# PSPS_AVNC_SRD_central-2020-10-12.net
KiCad netlist of a schematic drawn in EAGLE
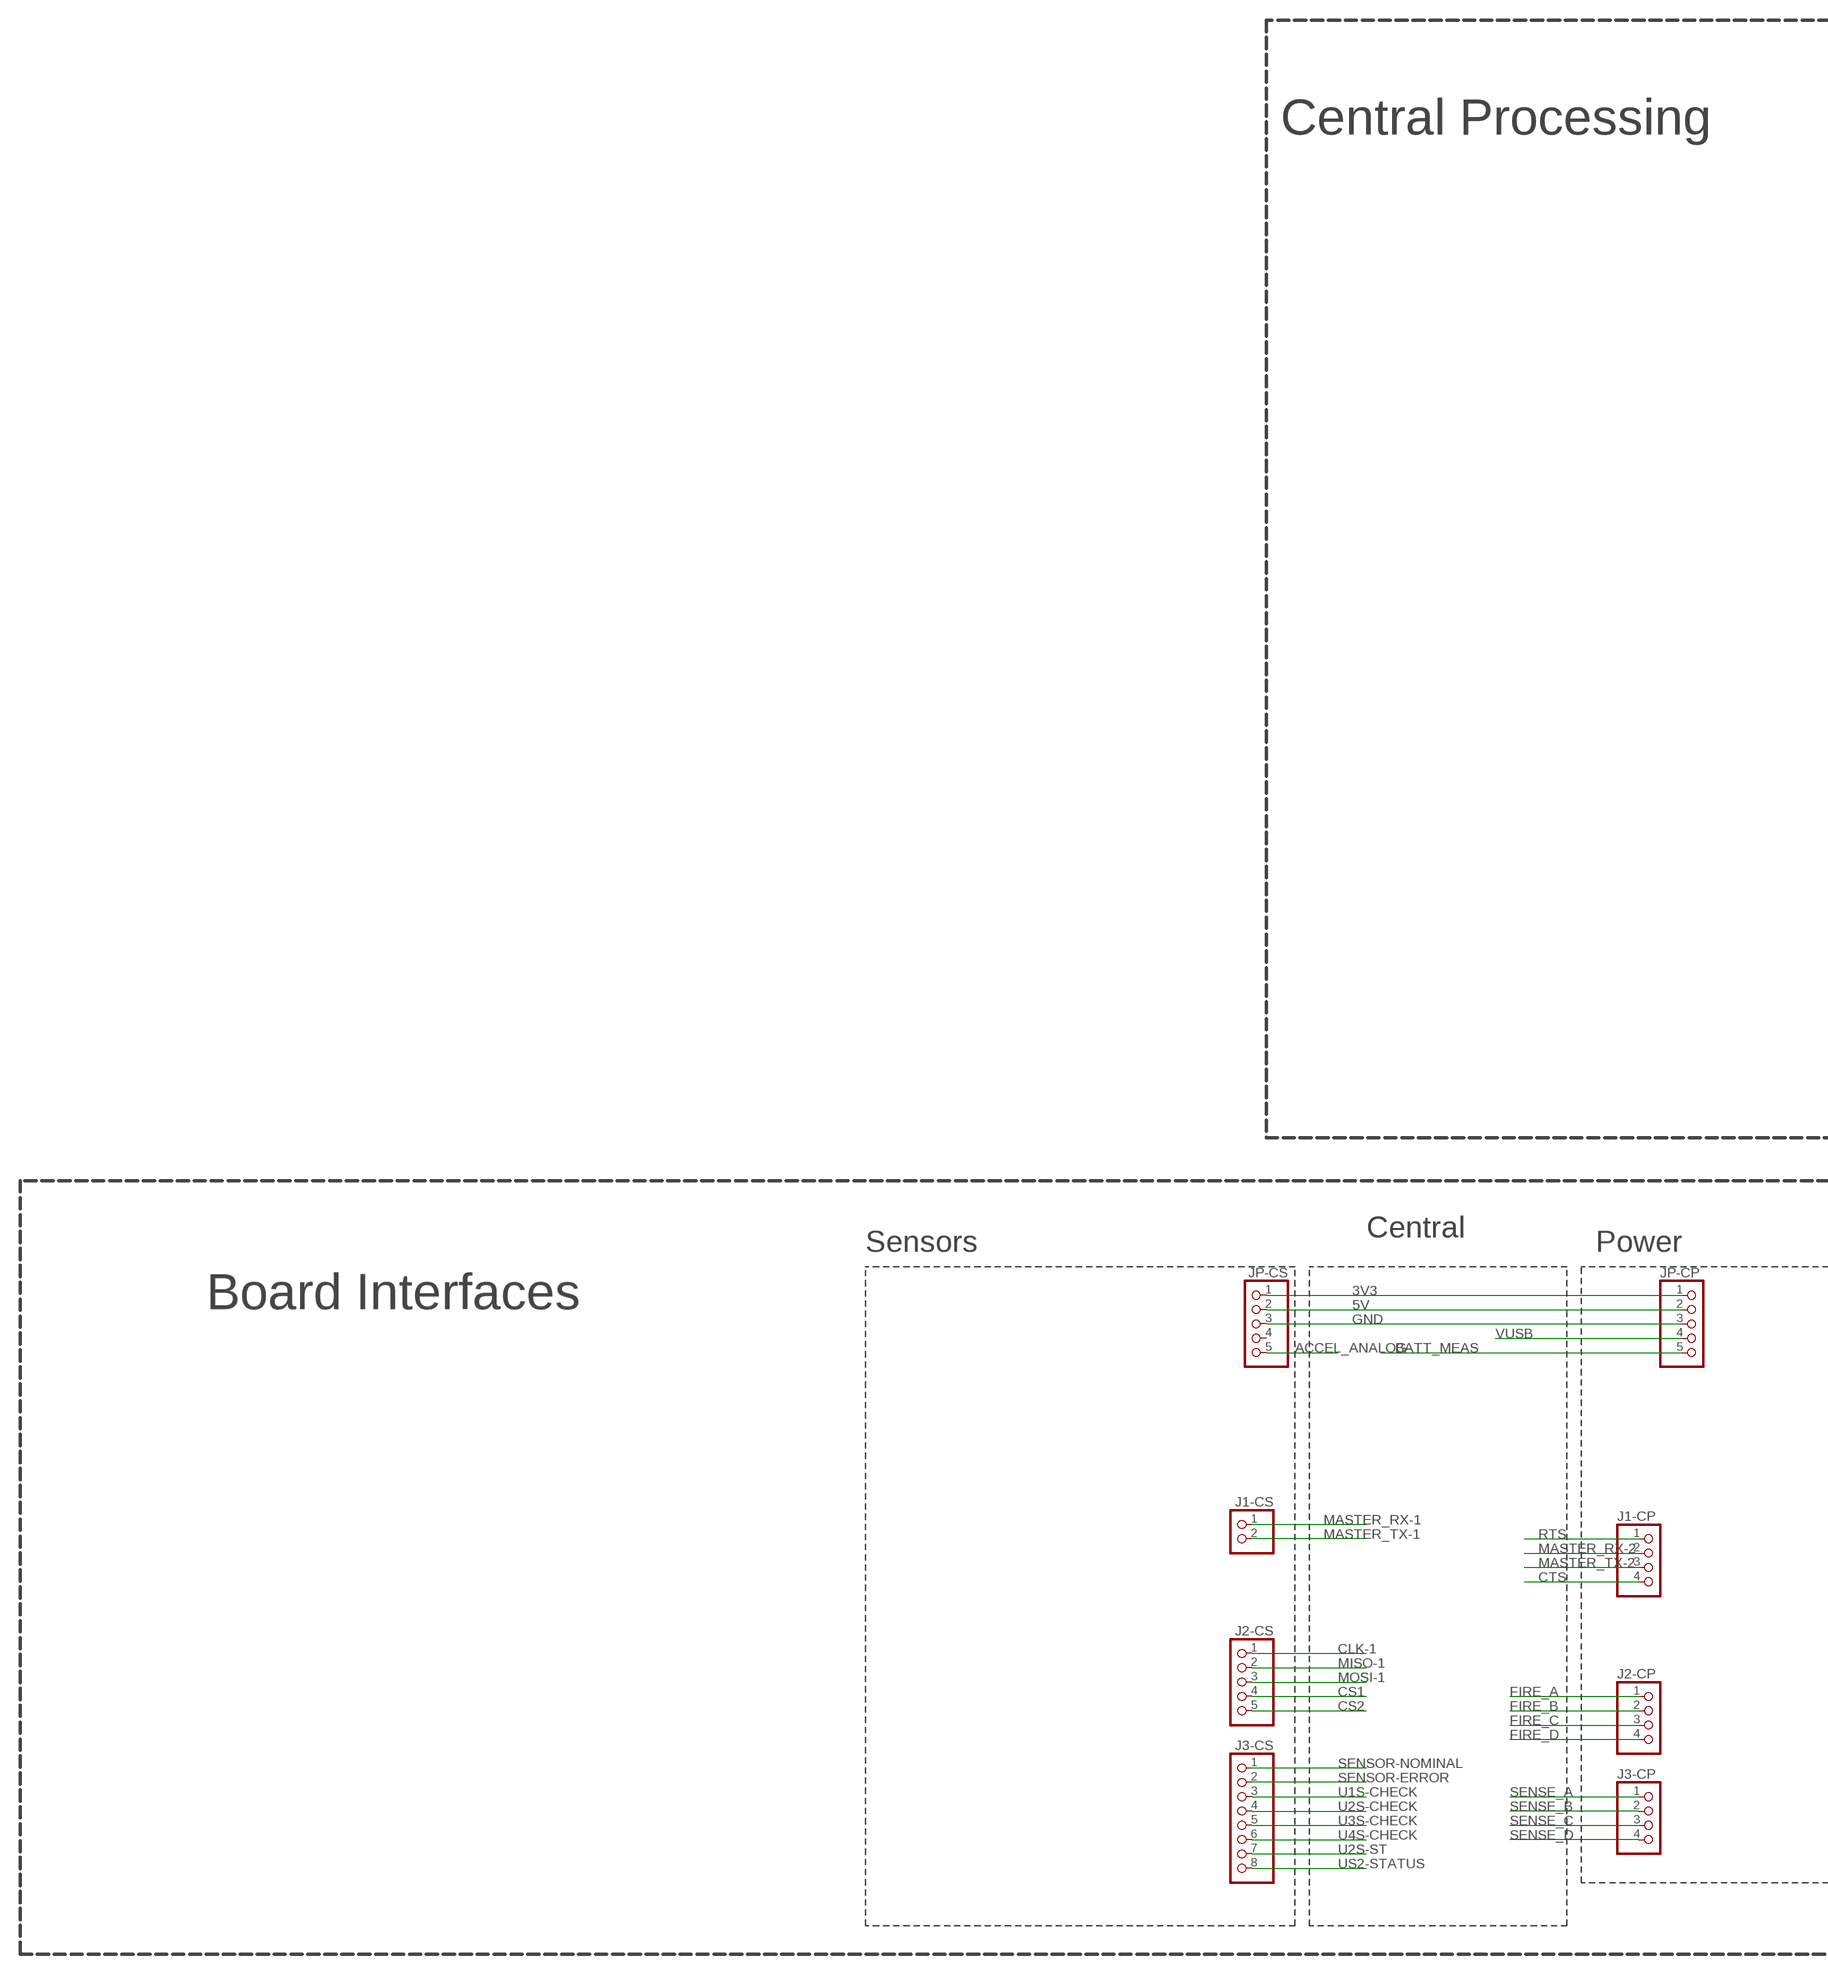
[diagram p0: schematic, sheet 1, part 1 of 2]
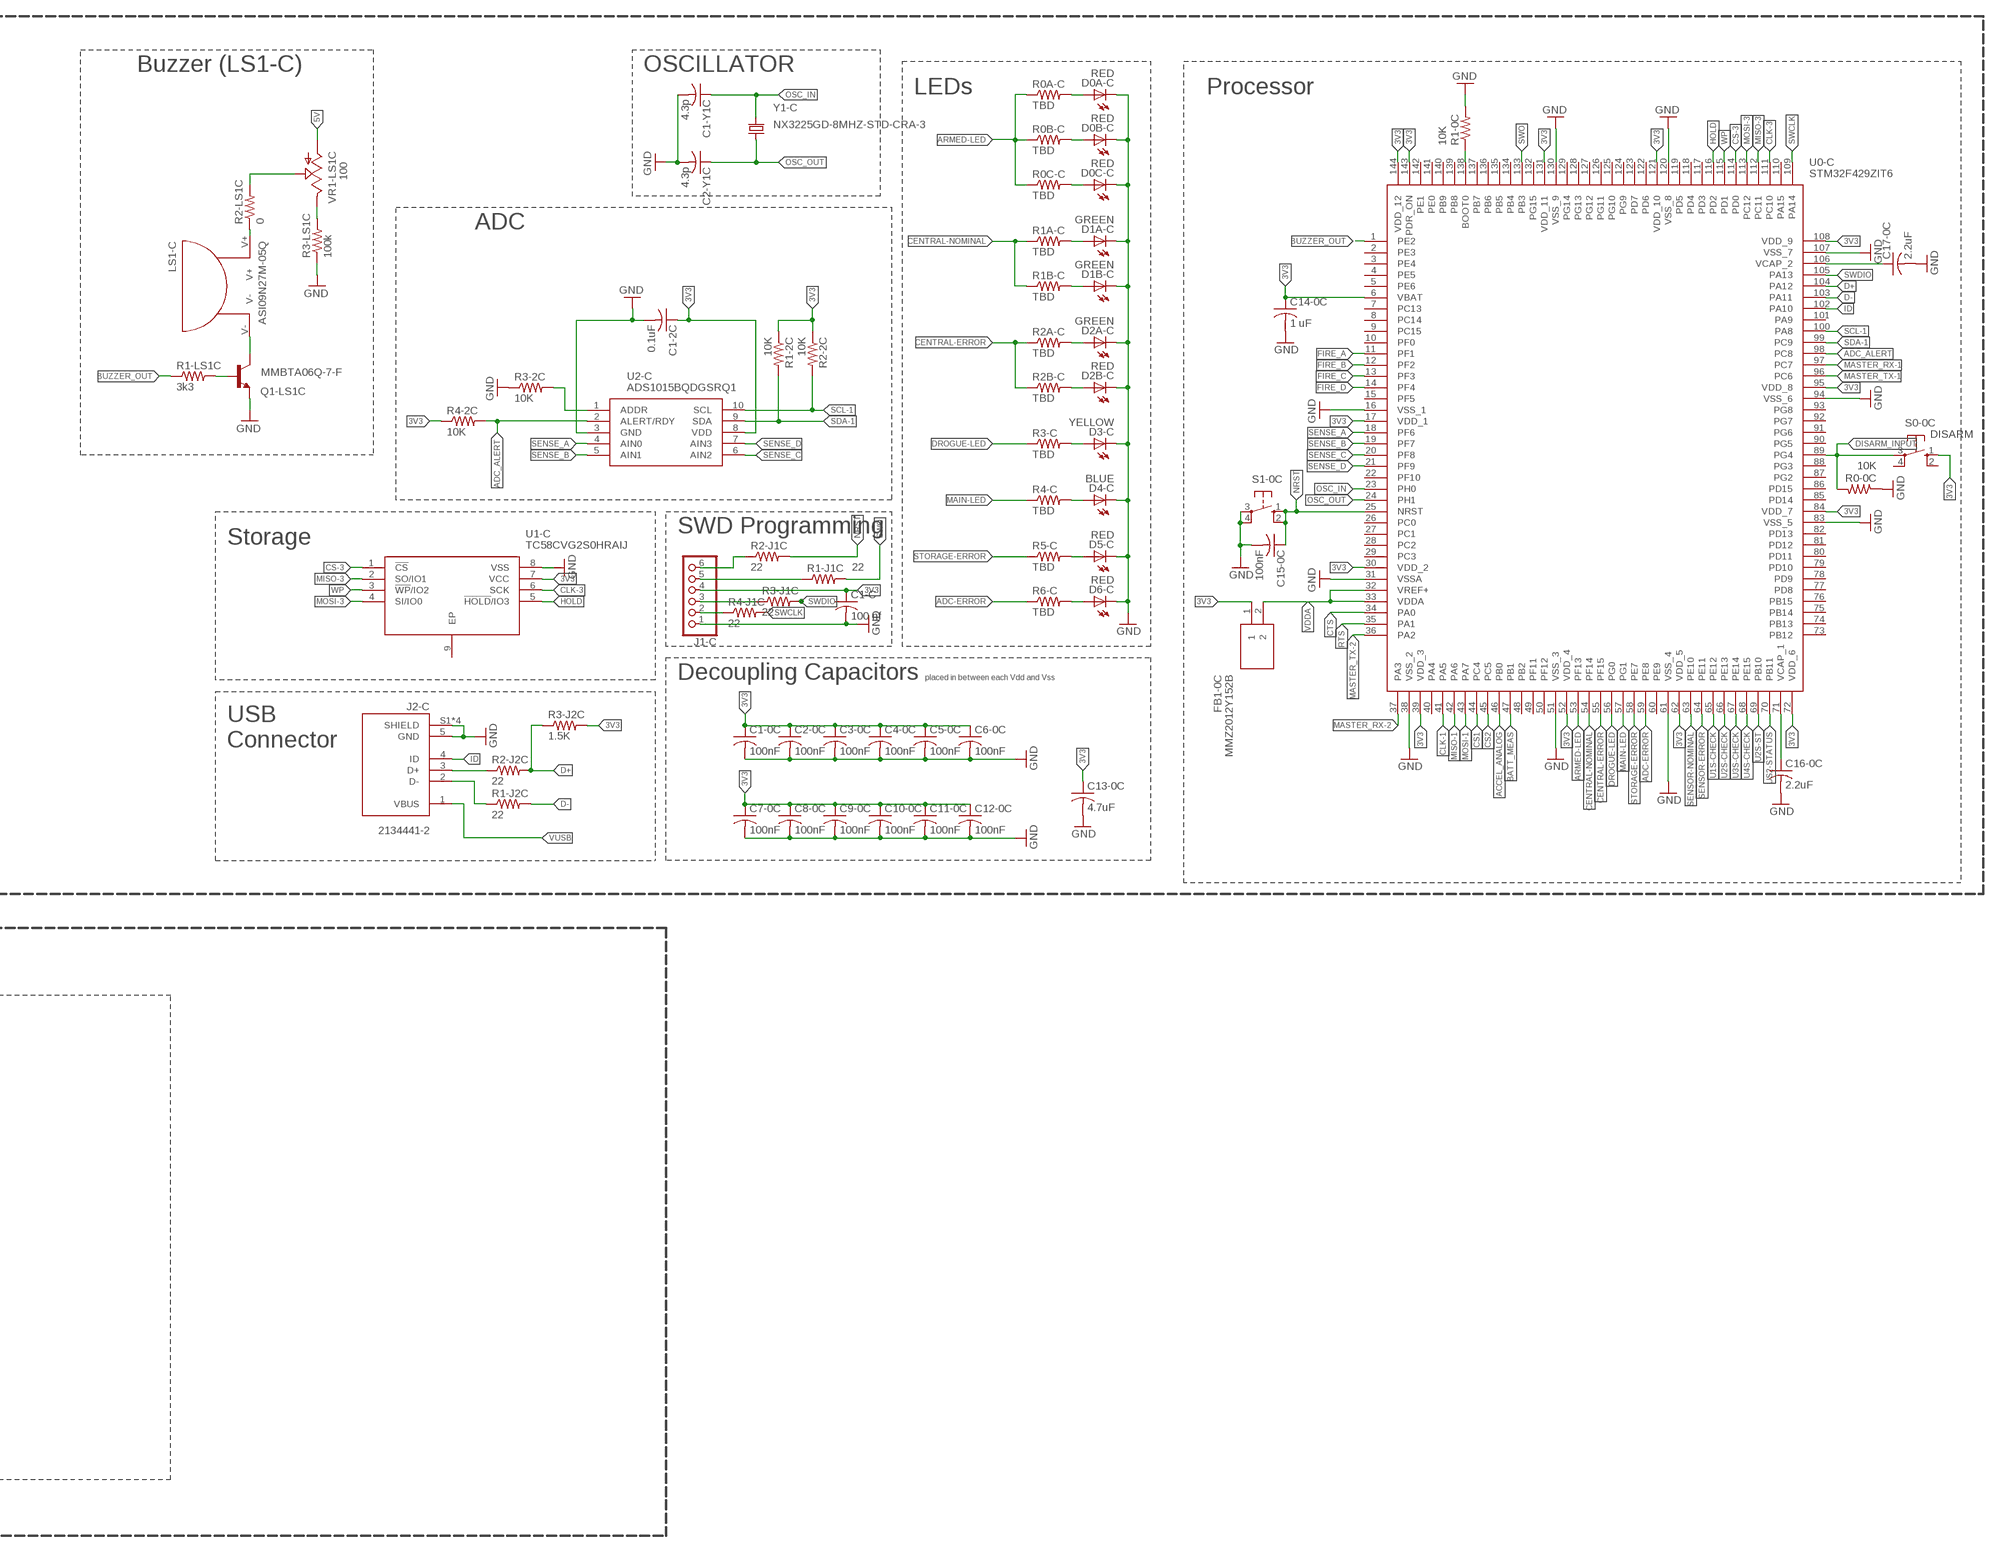
[diagram p1: schematic, sheet 1, part 2 of 2]

(export (version "E")
  (design (tool "Eeschema 10.0.6"))
  (components
    (comp (ref "C1-0C")
      (value "100nF")
      (footprint "eagle-import:C0805")
      (libsource (lib "eagle-import") (part "C-USC0805"))
    )
    (comp (ref "C1-2C")
      (value "0.1uF")
      (footprint "eagle-import:C0805")
      (libsource (lib "eagle-import") (part "C-USC0805"))
    )
    (comp (ref "C1-C")
      (value "100 nf")
      (footprint "eagle-import:C0805")
      (libsource (lib "eagle-import") (part "C-USC0805"))
    )
    (comp (ref "C1-Y1C")
      (value "4.3p")
      (footprint "eagle-import:C0805")
      (libsource (lib "eagle-import") (part "C-USC0805"))
    )
    (comp (ref "C2-0C")
      (value "100nF")
      (footprint "eagle-import:C0805")
      (libsource (lib "eagle-import") (part "C-USC0805"))
    )
    (comp (ref "C2-Y1C")
      (value "4.3p")
      (footprint "eagle-import:C0805")
      (libsource (lib "eagle-import") (part "C-USC0805"))
    )
    (comp (ref "C3-0C")
      (value "100nF")
      (footprint "eagle-import:C0805")
      (libsource (lib "eagle-import") (part "C-USC0805"))
    )
    (comp (ref "C4-0C")
      (value "100nF")
      (footprint "eagle-import:C0805")
      (libsource (lib "eagle-import") (part "C-USC0805"))
    )
    (comp (ref "C5-0C")
      (value "100nF")
      (footprint "eagle-import:C0805")
      (libsource (lib "eagle-import") (part "C-USC0805"))
    )
    (comp (ref "C6-0C")
      (value "100nF")
      (footprint "eagle-import:C0805")
      (libsource (lib "eagle-import") (part "C-USC0805"))
    )
    (comp (ref "C7-0C")
      (value "100nF")
      (footprint "eagle-import:C0805")
      (libsource (lib "eagle-import") (part "C-USC0805"))
    )
    (comp (ref "C8-0C")
      (value "100nF")
      (footprint "eagle-import:C0805")
      (libsource (lib "eagle-import") (part "C-USC0805"))
    )
    (comp (ref "C9-0C")
      (value "100nF")
      (footprint "eagle-import:C0805")
      (libsource (lib "eagle-import") (part "C-USC0805"))
    )
    (comp (ref "C10-0C")
      (value "100nF")
      (footprint "eagle-import:C0805")
      (libsource (lib "eagle-import") (part "C-USC0805"))
    )
    (comp (ref "C11-0C")
      (value "100nF")
      (footprint "eagle-import:C0805")
      (libsource (lib "eagle-import") (part "C-USC0805"))
    )
    (comp (ref "C12-0C")
      (value "100nF")
      (footprint "eagle-import:C0805")
      (libsource (lib "eagle-import") (part "C-USC0805"))
    )
    (comp (ref "C13-0C")
      (value "4.7uF")
      (footprint "eagle-import:C0805")
      (libsource (lib "eagle-import") (part "C-USC0805"))
    )
    (comp (ref "C14-0C")
      (value "1 uF")
      (footprint "eagle-import:C0805")
      (libsource (lib "eagle-import") (part "C-USC0805"))
    )
    (comp (ref "C15-0C")
      (value "100nF")
      (footprint "eagle-import:C0805")
      (libsource (lib "eagle-import") (part "C-USC0805"))
    )
    (comp (ref "C16-0C")
      (value "2.2uF")
      (footprint "eagle-import:C0805")
      (libsource (lib "eagle-import") (part "C-USC0805"))
    )
    (comp (ref "C17-0C")
      (value "2.2uF")
      (footprint "eagle-import:C0805")
      (libsource (lib "eagle-import") (part "C-USC0805"))
    )
    (comp (ref "D0A-C")
      (value "RED")
      (footprint "eagle-import:CHIPLED_0805")
      (libsource (lib "eagle-import") (part "LEDCHIPLED_0805"))
    )
    (comp (ref "D0B-C")
      (value "RED")
      (footprint "eagle-import:CHIPLED_0805")
      (libsource (lib "eagle-import") (part "LEDCHIPLED_0805"))
    )
    (comp (ref "D0C-C")
      (value "RED")
      (footprint "eagle-import:CHIPLED_0805")
      (libsource (lib "eagle-import") (part "LEDCHIPLED_0805"))
    )
    (comp (ref "D1A-C")
      (value "GREEN")
      (footprint "eagle-import:CHIPLED_0805")
      (libsource (lib "eagle-import") (part "LEDCHIPLED_0805"))
    )
    (comp (ref "D1B-C")
      (value "GREEN")
      (footprint "eagle-import:CHIPLED_0805")
      (libsource (lib "eagle-import") (part "LEDCHIPLED_0805"))
    )
    (comp (ref "D2A-C")
      (value "GREEN")
      (footprint "eagle-import:CHIPLED_0805")
      (libsource (lib "eagle-import") (part "LEDCHIPLED_0805"))
    )
    (comp (ref "D2B-C")
      (value "RED")
      (footprint "eagle-import:CHIPLED_0805")
      (libsource (lib "eagle-import") (part "LEDCHIPLED_0805"))
    )
    (comp (ref "D3-C")
      (value "YELLOW")
      (footprint "eagle-import:CHIPLED_0805")
      (libsource (lib "eagle-import") (part "LEDCHIPLED_0805"))
    )
    (comp (ref "D4-C")
      (value "BLUE")
      (footprint "eagle-import:CHIPLED_0805")
      (libsource (lib "eagle-import") (part "LEDCHIPLED_0805"))
    )
    (comp (ref "D5-C")
      (value "RED")
      (footprint "eagle-import:CHIPLED_0805")
      (libsource (lib "eagle-import") (part "LEDCHIPLED_0805"))
    )
    (comp (ref "D6-C")
      (value "RED")
      (footprint "eagle-import:CHIPLED_0805")
      (libsource (lib "eagle-import") (part "LEDCHIPLED_0805"))
    )
    (comp (ref "FB1-0C")
      (value "MMZ2012Y152B")
      (footprint "eagle-import:BEADC2012X105N")
      (fields (field (name "MOUSER_PART_NUMBER") "810-MMZ2012Y152B"))
      (libsource (lib "eagle-import") (part "MMZ2012Y152B"))
    )
    (comp (ref "J1-C")
      (value "PINHD-1X6")
      (footprint "eagle-import:1X06")
      (libsource (lib "eagle-import") (part "PINHD-1X6"))
    )
    (comp (ref "J1-CP")
      (value "PINHD-1X4")
      (footprint "eagle-import:1X04")
      (libsource (lib "eagle-import") (part "PINHD-1X4"))
    )
    (comp (ref "J1-CS")
      (value "PINHD-1X2")
      (footprint "eagle-import:1X02")
      (libsource (lib "eagle-import") (part "PINHD-1X2"))
    )
    (comp (ref "J2-C")
      (value "2134441-2")
      (footprint "eagle-import:TE_2134441-2")
      (fields (field (name "DIGI-KEY_PART_NUMBER") "A118104CT-ND") (field (name "MF") "TE Connectivity"))
      (libsource (lib "eagle-import") (part "2134441-2"))
    )
    (comp (ref "J2-CP")
      (value "PINHD-1X4")
      (footprint "eagle-import:1X04")
      (libsource (lib "eagle-import") (part "PINHD-1X4"))
    )
    (comp (ref "J2-CS")
      (value "PINHD-1X5")
      (footprint "eagle-import:1X05")
      (libsource (lib "eagle-import") (part "PINHD-1X5"))
    )
    (comp (ref "J3-CP")
      (value "PINHD-1X4")
      (footprint "eagle-import:1X04")
      (libsource (lib "eagle-import") (part "PINHD-1X4"))
    )
    (comp (ref "J3-CS")
      (value "PINHD-1X8")
      (footprint "eagle-import:1X08")
      (libsource (lib "eagle-import") (part "PINHD-1X8"))
    )
    (comp (ref "JP-CP")
      (value "PINHD-1X5")
      (footprint "eagle-import:1X05")
      (libsource (lib "eagle-import") (part "PINHD-1X5"))
    )
    (comp (ref "JP-CS")
      (value "PINHD-1X5")
      (footprint "eagle-import:1X05")
      (libsource (lib "eagle-import") (part "PINHD-1X5"))
    )
    (comp (ref "LS1-C")
      (value "ASI09N27M-05Q")
      (footprint "eagle-import:ASI09N27M-05Q")
      (libsource (lib "eagle-import") (part "ASI09N27M-05Q"))
    )
    (comp (ref "Q1-LS1C")
      (value "MMBTA06Q-7-F")
      (footprint "eagle-import:SOT23")
      (libsource (lib "eagle-import") (part "NPN_TRANSISTOR"))
    )
    (comp (ref "R0-0C")
      (value "10K")
      (footprint "eagle-import:R0805")
      (libsource (lib "eagle-import") (part "R-US_R0805"))
    )
    (comp (ref "R0A-C")
      (value "TBD")
      (footprint "eagle-import:M0805")
      (libsource (lib "eagle-import") (part "R-US_M0805"))
    )
    (comp (ref "R0B-C")
      (value "TBD")
      (footprint "eagle-import:M0805")
      (libsource (lib "eagle-import") (part "R-US_M0805"))
    )
    (comp (ref "R0C-C")
      (value "TBD")
      (footprint "eagle-import:M0805")
      (libsource (lib "eagle-import") (part "R-US_M0805"))
    )
    (comp (ref "R1-0C")
      (value "10K")
      (footprint "eagle-import:R0805")
      (libsource (lib "eagle-import") (part "R-US_R0805"))
    )
    (comp (ref "R1-2C")
      (value "10K")
      (footprint "eagle-import:R0805")
      (libsource (lib "eagle-import") (part "R-US_R0805"))
    )
    (comp (ref "R1-J1C")
      (value "22")
      (footprint "eagle-import:M0805")
      (libsource (lib "eagle-import") (part "R-US_M0805"))
    )
    (comp (ref "R1-J2C")
      (value "22")
      (footprint "eagle-import:M0805")
      (libsource (lib "eagle-import") (part "R-US_M0805"))
    )
    (comp (ref "R1-LS1C")
      (value "3k3")
      (footprint "eagle-import:R0805")
      (libsource (lib "eagle-import") (part "resistor_348_R-US_R0805"))
    )
    (comp (ref "R1A-C")
      (value "TBD")
      (footprint "eagle-import:M0805")
      (libsource (lib "eagle-import") (part "R-US_M0805"))
    )
    (comp (ref "R1B-C")
      (value "TBD")
      (footprint "eagle-import:M0805")
      (libsource (lib "eagle-import") (part "R-US_M0805"))
    )
    (comp (ref "R2-2C")
      (value "10K")
      (footprint "eagle-import:R0805")
      (libsource (lib "eagle-import") (part "R-US_R0805"))
    )
    (comp (ref "R2-J1C")
      (value "22")
      (footprint "eagle-import:M0805")
      (libsource (lib "eagle-import") (part "R-US_M0805"))
    )
    (comp (ref "R2-J2C")
      (value "22")
      (footprint "eagle-import:M0805")
      (libsource (lib "eagle-import") (part "R-US_M0805"))
    )
    (comp (ref "R2-LS1C")
      (value "0")
      (footprint "eagle-import:R0805")
      (libsource (lib "eagle-import") (part "resistor_348_R-US_R0805"))
    )
    (comp (ref "R2A-C")
      (value "TBD")
      (footprint "eagle-import:M0805")
      (libsource (lib "eagle-import") (part "R-US_M0805"))
    )
    (comp (ref "R2B-C")
      (value "TBD")
      (footprint "eagle-import:M0805")
      (libsource (lib "eagle-import") (part "R-US_M0805"))
    )
    (comp (ref "R3-2C")
      (value "10K")
      (footprint "eagle-import:R0805")
      (libsource (lib "eagle-import") (part "R-US_R0805"))
    )
    (comp (ref "R3-C")
      (value "TBD")
      (footprint "eagle-import:M0805")
      (libsource (lib "eagle-import") (part "R-US_M0805"))
    )
    (comp (ref "R3-J1C")
      (value "22")
      (footprint "eagle-import:M0805")
      (libsource (lib "eagle-import") (part "R-US_M0805"))
    )
    (comp (ref "R3-J2C")
      (value "1.5K")
      (footprint "eagle-import:M0805")
      (libsource (lib "eagle-import") (part "R-US_M0805"))
    )
    (comp (ref "R3-LS1C")
      (value "100k")
      (footprint "eagle-import:R0805")
      (libsource (lib "eagle-import") (part "resistor_348_R-US_R0805"))
    )
    (comp (ref "R4-2C")
      (value "10K")
      (footprint "eagle-import:R0805")
      (libsource (lib "eagle-import") (part "R-US_R0805"))
    )
    (comp (ref "R4-C")
      (value "TBD")
      (footprint "eagle-import:M0805")
      (libsource (lib "eagle-import") (part "R-US_M0805"))
    )
    (comp (ref "R4-J1C")
      (value "22")
      (footprint "eagle-import:M0805")
      (libsource (lib "eagle-import") (part "R-US_M0805"))
    )
    (comp (ref "R5-C")
      (value "TBD")
      (footprint "eagle-import:M0805")
      (libsource (lib "eagle-import") (part "R-US_M0805"))
    )
    (comp (ref "R6-C")
      (value "TBD")
      (footprint "eagle-import:M0805")
      (libsource (lib "eagle-import") (part "R-US_M0805"))
    )
    (comp (ref "S0-0C")
      (value "DISARM")
      (footprint "eagle-import:B3F-10XX")
      (fields (field (name "MPN") "B3F-1000"))
      (libsource (lib "eagle-import") (part "10-XX"))
    )
    (comp (ref "S1-0C")
      (value "10-XX")
      (footprint "eagle-import:B3F-10XX")
      (fields (field (name "MPN") "B3F-1000"))
      (libsource (lib "eagle-import") (part "10-XX"))
    )
    (comp (ref "U0-C")
      (value "STM32F429ZIT6")
      (footprint "eagle-import:QFP50P2200X2200X160-144N")
      (fields (field (name "MOUSER_PART_NUMBER") "511-STM32F429ZIT6"))
      (libsource (lib "eagle-import") (part "STM32F429ZIT6"))
    )
    (comp (ref "U1-C")
      (value "TC58CVG2S0HRAIJ")
      (footprint "eagle-import:SON127P800X600X80-9N")
      (fields (field (name "MOUSER_PART_NUMBER") "757-TC58CVG2S0HRAIJ"))
      (libsource (lib "eagle-import") (part "TC58CVG2S0HRAIJ"))
    )
    (comp (ref "U2-C")
      (value "ADS1015BQDGSRQ1")
      (footprint "eagle-import:SOP50P490X110-10N")
      (fields (field (name "MOUSER_PART_NUMBER") "595-ADS1015BQDGSRQ1"))
      (libsource (lib "eagle-import") (part "ADS1015BQDGSRQ1"))
    )
    (comp (ref "VR1-LS1C")
      (value "100")
      (footprint "eagle-import:LI10")
      (libsource (lib "eagle-import") (part "TRIM_US-LI10"))
    )
    (comp (ref "Y1-C")
      (value "NX3225GD-8MHZ-STD-CRA-3")
      (footprint "eagle-import:NX3225GD")
      (libsource (lib "eagle-import") (part "NX3225GD"))
    )
  )
  (nets
    (net (code "1") (name "3V3") (class "Default")
      (node (ref "C1-0C") (pin "1") (pinfunction "1_1") (pintype "passive"))
      (node (ref "C1-2C") (pin "1") (pinfunction "1_1") (pintype "passive"))
      (node (ref "C1-C") (pin "1") (pinfunction "1_1") (pintype "passive"))
      (node (ref "C10-0C") (pin "1") (pinfunction "1_1") (pintype "passive"))
      (node (ref "C11-0C") (pin "1") (pinfunction "1_1") (pintype "passive"))
      (node (ref "C12-0C") (pin "1") (pinfunction "1_1") (pintype "passive"))
      (node (ref "C13-0C") (pin "1") (pinfunction "1_1") (pintype "passive"))
      (node (ref "C14-0C") (pin "1") (pinfunction "1_1") (pintype "passive"))
      (node (ref "C2-0C") (pin "1") (pinfunction "1_1") (pintype "passive"))
      (node (ref "C3-0C") (pin "1") (pinfunction "1_1") (pintype "passive"))
      (node (ref "C4-0C") (pin "1") (pinfunction "1_1") (pintype "passive"))
      (node (ref "C5-0C") (pin "1") (pinfunction "1_1") (pintype "passive"))
      (node (ref "C6-0C") (pin "1") (pinfunction "1_1") (pintype "passive"))
      (node (ref "C7-0C") (pin "1") (pinfunction "1_1") (pintype "passive"))
      (node (ref "C8-0C") (pin "1") (pinfunction "1_1") (pintype "passive"))
      (node (ref "C9-0C") (pin "1") (pinfunction "1_1") (pintype "passive"))
      (node (ref "FB1-0C") (pin "1") (pinfunction "1_1") (pintype "bidirectional"))
      (node (ref "J1-C") (pin "4") (pinfunction "4_4") (pintype "passive"))
      (node (ref "JP-CP") (pin "1") (pinfunction "1_1") (pintype "passive"))
      (node (ref "JP-CS") (pin "1") (pinfunction "1_1") (pintype "passive"))
      (node (ref "R1-2C") (pin "1") (pinfunction "1_1") (pintype "passive"))
      (node (ref "R2-2C") (pin "1") (pinfunction "1_1") (pintype "passive"))
      (node (ref "R3-J2C") (pin "2") (pinfunction "2_2") (pintype "passive"))
      (node (ref "R4-2C") (pin "1") (pinfunction "1_1") (pintype "passive"))
      (node (ref "S0-0C") (pin "1") (pinfunction "S_1") (pintype "passive"))
      (node (ref "U0-C") (pin "108") (pinfunction "VDD_9_108") (pintype "power_in"))
      (node (ref "U0-C") (pin "121") (pinfunction "VDD_10_121") (pintype "power_in"))
      (node (ref "U0-C") (pin "131") (pinfunction "VDD_11_131") (pintype "power_in"))
      (node (ref "U0-C") (pin "143") (pinfunction "PDR_ON_143") (pintype "bidirectional"))
      (node (ref "U0-C") (pin "144") (pinfunction "VDD_12_144") (pintype "power_in"))
      (node (ref "U0-C") (pin "17") (pinfunction "VDD_1_17") (pintype "power_in"))
      (node (ref "U0-C") (pin "30") (pinfunction "VDD_2_30") (pintype "power_in"))
      (node (ref "U0-C") (pin "39") (pinfunction "VDD_3_39") (pintype "power_in"))
      (node (ref "U0-C") (pin "52") (pinfunction "VDD_4_52") (pintype "power_in"))
      (node (ref "U0-C") (pin "6") (pinfunction "VBAT_6") (pintype "bidirectional"))
      (node (ref "U0-C") (pin "62") (pinfunction "VDD_5_62") (pintype "power_in"))
      (node (ref "U0-C") (pin "72") (pinfunction "VDD_6_72") (pintype "power_in"))
      (node (ref "U0-C") (pin "84") (pinfunction "VDD_7_84") (pintype "power_in"))
      (node (ref "U0-C") (pin "95") (pinfunction "VDD_8_95") (pintype "power_in"))
      (node (ref "U1-C") (pin "7") (pinfunction "VCC_7") (pintype "bidirectional"))
      (node (ref "U2-C") (pin "8") (pinfunction "VDD_8") (pintype "bidirectional"))
    )
    (net (code "2") (name "5V") (class "Default")
      (node (ref "JP-CP") (pin "2") (pinfunction "2_2") (pintype "passive"))
      (node (ref "JP-CS") (pin "2") (pinfunction "2_2") (pintype "passive"))
      (node (ref "VR1-LS1C") (pin "A") (pinfunction "A_A") (pintype "passive"))
    )
    (net (code "3") (name "ACCEL_ANALOG") (class "Default")
      (node (ref "JP-CS") (pin "5") (pinfunction "5_5") (pintype "passive"))
      (node (ref "U0-C") (pin "46") (pinfunction "PB0_46") (pintype "bidirectional"))
    )
    (net (code "4") (name "ADC-ERROR") (class "Default")
      (node (ref "R6-C") (pin "1") (pinfunction "1_1") (pintype "passive"))
      (node (ref "U0-C") (pin "59") (pinfunction "PE8_59") (pintype "bidirectional"))
    )
    (net (code "5") (name "ADC_ALERT") (class "Default")
      (node (ref "R4-2C") (pin "2") (pinfunction "2_2") (pintype "passive"))
      (node (ref "U0-C") (pin "98") (pinfunction "PC8_98") (pintype "bidirectional"))
      (node (ref "U2-C") (pin "2") (pinfunction "ALERT/RDY_2") (pintype "bidirectional"))
    )
    (net (code "6") (name "ARMED-LED") (class "Default")
      (node (ref "R0A-C") (pin "1") (pinfunction "1_1") (pintype "passive"))
      (node (ref "R0B-C") (pin "1") (pinfunction "1_1") (pintype "passive"))
      (node (ref "R0C-C") (pin "1") (pinfunction "1_1") (pintype "passive"))
      (node (ref "U0-C") (pin "53") (pinfunction "PF13_53") (pintype "bidirectional"))
    )
    (net (code "7") (name "BATT_MEAS") (class "Default")
      (node (ref "JP-CP") (pin "5") (pinfunction "5_5") (pintype "passive"))
      (node (ref "U0-C") (pin "47") (pinfunction "PB1_47") (pintype "bidirectional"))
    )
    (net (code "8") (name "BUZZER_OUT") (class "Default")
      (node (ref "R1-LS1C") (pin "1") (pinfunction "1_1") (pintype "passive"))
      (node (ref "U0-C") (pin "1") (pinfunction "PE2_1") (pintype "bidirectional"))
    )
    (net (code "9") (name "CENTRAL-ERROR") (class "Default")
      (node (ref "R2A-C") (pin "1") (pinfunction "1_1") (pintype "passive"))
      (node (ref "R2B-C") (pin "1") (pinfunction "1_1") (pintype "passive"))
      (node (ref "U0-C") (pin "55") (pinfunction "PF15_55") (pintype "bidirectional"))
    )
    (net (code "10") (name "CENTRAL-NOMINAL") (class "Default")
      (node (ref "R1A-C") (pin "1") (pinfunction "1_1") (pintype "passive"))
      (node (ref "R1B-C") (pin "1") (pinfunction "1_1") (pintype "passive"))
      (node (ref "U0-C") (pin "54") (pinfunction "PF14_54") (pintype "bidirectional"))
    )
    (net (code "11") (name "CLK-1") (class "Default")
      (node (ref "J2-CS") (pin "1") (pinfunction "1_1") (pintype "passive"))
      (node (ref "U0-C") (pin "41") (pinfunction "PA5_41") (pintype "bidirectional"))
    )
    (net (code "12") (name "CLK-3") (class "Default")
      (node (ref "U0-C") (pin "111") (pinfunction "PC10_111") (pintype "bidirectional"))
      (node (ref "U1-C") (pin "6") (pinfunction "SCK_6") (pintype "bidirectional"))
    )
    (net (code "13") (name "CS-3") (class "Default")
      (node (ref "U0-C") (pin "114") (pinfunction "PD0_114") (pintype "bidirectional"))
      (node (ref "U1-C") (pin "1") (pinfunction "~{CS}_1") (pintype "bidirectional"))
    )
    (net (code "14") (name "CS1") (class "Default")
      (node (ref "J2-CS") (pin "4") (pinfunction "4_4") (pintype "passive"))
      (node (ref "U0-C") (pin "44") (pinfunction "PC4_44") (pintype "bidirectional"))
    )
    (net (code "15") (name "CS2") (class "Default")
      (node (ref "J2-CS") (pin "5") (pinfunction "5_5") (pintype "passive"))
      (node (ref "U0-C") (pin "45") (pinfunction "PC5_45") (pintype "bidirectional"))
    )
    (net (code "16") (name "CTS") (class "Default")
      (node (ref "J1-CP") (pin "4") (pinfunction "4_4") (pintype "passive"))
      (node (ref "U0-C") (pin "34") (pinfunction "PA0_34") (pintype "bidirectional"))
    )
    (net (code "17") (name "D+") (class "Default")
      (node (ref "R2-J2C") (pin "2") (pinfunction "2_2") (pintype "passive"))
      (node (ref "R3-J2C") (pin "1") (pinfunction "1_1") (pintype "passive"))
      (node (ref "U0-C") (pin "104") (pinfunction "PA12_104") (pintype "bidirectional"))
    )
    (net (code "18") (name "D-") (class "Default")
      (node (ref "R1-J2C") (pin "2") (pinfunction "2_2") (pintype "passive"))
      (node (ref "U0-C") (pin "103") (pinfunction "PA11_103") (pintype "bidirectional"))
    )
    (net (code "19") (name "DISARM_INPUT") (class "Default")
      (node (ref "R0-0C") (pin "2") (pinfunction "2_2") (pintype "passive"))
      (node (ref "S0-0C") (pin "3") (pinfunction "P_3") (pintype "passive"))
      (node (ref "U0-C") (pin "89") (pinfunction "PG4_89") (pintype "bidirectional"))
    )
    (net (code "20") (name "DROGUE-LED") (class "Default")
      (node (ref "R3-C") (pin "1") (pinfunction "1_1") (pintype "passive"))
      (node (ref "U0-C") (pin "56") (pinfunction "PG0_56") (pintype "bidirectional"))
    )
    (net (code "21") (name "FIRE_A") (class "Default")
      (node (ref "J2-CP") (pin "1") (pinfunction "1_1") (pintype "passive"))
      (node (ref "U0-C") (pin "11") (pinfunction "PF1_11") (pintype "bidirectional"))
    )
    (net (code "22") (name "FIRE_B") (class "Default")
      (node (ref "J2-CP") (pin "2") (pinfunction "2_2") (pintype "passive"))
      (node (ref "U0-C") (pin "12") (pinfunction "PF2_12") (pintype "bidirectional"))
    )
    (net (code "23") (name "FIRE_C") (class "Default")
      (node (ref "J2-CP") (pin "3") (pinfunction "3_3") (pintype "passive"))
      (node (ref "U0-C") (pin "13") (pinfunction "PF3_13") (pintype "bidirectional"))
    )
    (net (code "24") (name "FIRE_D") (class "Default")
      (node (ref "J2-CP") (pin "4") (pinfunction "4_4") (pintype "passive"))
      (node (ref "U0-C") (pin "14") (pinfunction "PF4_14") (pintype "bidirectional"))
    )
    (net (code "25") (name "GND") (class "Default")
      (node (ref "C1-0C") (pin "2") (pinfunction "2_2") (pintype "passive"))
      (node (ref "C1-2C") (pin "2") (pinfunction "2_2") (pintype "passive"))
      (node (ref "C1-C") (pin "2") (pinfunction "2_2") (pintype "passive"))
      (node (ref "C1-Y1C") (pin "2") (pinfunction "2_2") (pintype "passive"))
      (node (ref "C10-0C") (pin "2") (pinfunction "2_2") (pintype "passive"))
      (node (ref "C11-0C") (pin "2") (pinfunction "2_2") (pintype "passive"))
      (node (ref "C12-0C") (pin "2") (pinfunction "2_2") (pintype "passive"))
      (node (ref "C13-0C") (pin "2") (pinfunction "2_2") (pintype "passive"))
      (node (ref "C14-0C") (pin "2") (pinfunction "2_2") (pintype "passive"))
      (node (ref "C15-0C") (pin "2") (pinfunction "2_2") (pintype "passive"))
      (node (ref "C16-0C") (pin "2") (pinfunction "2_2") (pintype "passive"))
      (node (ref "C17-0C") (pin "2") (pinfunction "2_2") (pintype "passive"))
      (node (ref "C2-0C") (pin "2") (pinfunction "2_2") (pintype "passive"))
      (node (ref "C2-Y1C") (pin "2") (pinfunction "2_2") (pintype "passive"))
      (node (ref "C3-0C") (pin "2") (pinfunction "2_2") (pintype "passive"))
      (node (ref "C4-0C") (pin "2") (pinfunction "2_2") (pintype "passive"))
      (node (ref "C5-0C") (pin "2") (pinfunction "2_2") (pintype "passive"))
      (node (ref "C6-0C") (pin "2") (pinfunction "2_2") (pintype "passive"))
      (node (ref "C7-0C") (pin "2") (pinfunction "2_2") (pintype "passive"))
      (node (ref "C8-0C") (pin "2") (pinfunction "2_2") (pintype "passive"))
      (node (ref "C9-0C") (pin "2") (pinfunction "2_2") (pintype "passive"))
      (node (ref "D0A-C") (pin "C") (pinfunction "C_C") (pintype "passive"))
      (node (ref "D0B-C") (pin "C") (pinfunction "C_C") (pintype "passive"))
      (node (ref "D0C-C") (pin "C") (pinfunction "C_C") (pintype "passive"))
      (node (ref "D1A-C") (pin "C") (pinfunction "C_C") (pintype "passive"))
      (node (ref "D1B-C") (pin "C") (pinfunction "C_C") (pintype "passive"))
      (node (ref "D2A-C") (pin "C") (pinfunction "C_C") (pintype "passive"))
      (node (ref "D2B-C") (pin "C") (pinfunction "C_C") (pintype "passive"))
      (node (ref "D3-C") (pin "C") (pinfunction "C_C") (pintype "passive"))
      (node (ref "D4-C") (pin "C") (pinfunction "C_C") (pintype "passive"))
      (node (ref "D5-C") (pin "C") (pinfunction "C_C") (pintype "passive"))
      (node (ref "D6-C") (pin "C") (pinfunction "C_C") (pintype "passive"))
      (node (ref "J1-C") (pin "1") (pinfunction "1_1") (pintype "passive"))
      (node (ref "J2-C") (pin "5") (pinfunction "GND_5") (pintype "power_in"))
      (node (ref "J2-C") (pin "S1") (pinfunction "SHIELD_S1") (pintype "power_in"))
      (node (ref "J2-C") (pin "S2") (pinfunction "SHIELD_S2") (pintype "power_in"))
      (node (ref "J2-C") (pin "S3") (pinfunction "SHIELD_S3") (pintype "power_in"))
      (node (ref "J2-C") (pin "S4") (pinfunction "SHIELD_S4") (pintype "power_in"))
      (node (ref "JP-CP") (pin "3") (pinfunction "3_3") (pintype "passive"))
      (node (ref "JP-CS") (pin "3") (pinfunction "3_3") (pintype "passive"))
      (node (ref "Q1-LS1C") (pin "3") (pinfunction "E_3") (pintype "passive"))
      (node (ref "R0-0C") (pin "1") (pinfunction "1_1") (pintype "passive"))
      (node (ref "R1-0C") (pin "2") (pinfunction "2_2") (pintype "passive"))
      (node (ref "R3-2C") (pin "1") (pinfunction "1_1") (pintype "passive"))
      (node (ref "R3-LS1C") (pin "1") (pinfunction "1_1") (pintype "passive"))
      (node (ref "S1-0C") (pin "3") (pinfunction "P_3") (pintype "passive"))
      (node (ref "S1-0C") (pin "4") (pinfunction "P1_4") (pintype "passive"))
      (node (ref "U0-C") (pin "107") (pinfunction "VSS_7_107") (pintype "power_in"))
      (node (ref "U0-C") (pin "120") (pinfunction "VSS_8_120") (pintype "power_in"))
      (node (ref "U0-C") (pin "130") (pinfunction "VSS_9_130") (pintype "power_in"))
      (node (ref "U0-C") (pin "16") (pinfunction "VSS_1_16") (pintype "power_in"))
      (node (ref "U0-C") (pin "31") (pinfunction "VSSA_31") (pintype "power_in"))
      (node (ref "U0-C") (pin "38") (pinfunction "VSS_2_38") (pintype "power_in"))
      (node (ref "U0-C") (pin "51") (pinfunction "VSS_3_51") (pintype "power_in"))
      (node (ref "U0-C") (pin "61") (pinfunction "VSS_4_61") (pintype "power_in"))
      (node (ref "U0-C") (pin "83") (pinfunction "VSS_5_83") (pintype "power_in"))
      (node (ref "U0-C") (pin "94") (pinfunction "VSS_6_94") (pintype "power_in"))
      (node (ref "U1-C") (pin "8") (pinfunction "VSS_8") (pintype "bidirectional"))
      (node (ref "U2-C") (pin "3") (pinfunction "GND_3") (pintype "bidirectional"))
    )
    (net (code "26") (name "HOLD") (class "Default")
      (node (ref "U0-C") (pin "116") (pinfunction "PD2_116") (pintype "bidirectional"))
      (node (ref "U1-C") (pin "5") (pinfunction "~{HOLD}/IO3_5") (pintype "bidirectional"))
    )
    (net (code "27") (name "ID") (class "Default")
      (node (ref "J2-C") (pin "4") (pinfunction "ID_4") (pintype "bidirectional"))
      (node (ref "U0-C") (pin "102") (pinfunction "PA10_102") (pintype "bidirectional"))
    )
    (net (code "28") (name "MAIN-LED") (class "Default")
      (node (ref "R4-C") (pin "1") (pinfunction "1_1") (pintype "passive"))
      (node (ref "U0-C") (pin "57") (pinfunction "PG1_57") (pintype "bidirectional"))
    )
    (net (code "29") (name "MASTER_RX-1") (class "Default")
      (node (ref "J1-CS") (pin "1") (pinfunction "1_1") (pintype "passive"))
      (node (ref "U0-C") (pin "97") (pinfunction "PC7_97") (pintype "bidirectional"))
    )
    (net (code "30") (name "MASTER_RX-2") (class "Default")
      (node (ref "J1-CP") (pin "2") (pinfunction "2_2") (pintype "passive"))
      (node (ref "U0-C") (pin "37") (pinfunction "PA3_37") (pintype "bidirectional"))
    )
    (net (code "31") (name "MASTER_TX-1") (class "Default")
      (node (ref "J1-CS") (pin "2") (pinfunction "2_2") (pintype "passive"))
      (node (ref "U0-C") (pin "96") (pinfunction "PC6_96") (pintype "bidirectional"))
    )
    (net (code "32") (name "MASTER_TX-2") (class "Default")
      (node (ref "J1-CP") (pin "3") (pinfunction "3_3") (pintype "passive"))
      (node (ref "U0-C") (pin "36") (pinfunction "PA2_36") (pintype "bidirectional"))
    )
    (net (code "33") (name "MISO-1") (class "Default")
      (node (ref "J2-CS") (pin "2") (pinfunction "2_2") (pintype "passive"))
      (node (ref "U0-C") (pin "42") (pinfunction "PA6_42") (pintype "bidirectional"))
    )
    (net (code "34") (name "MISO-3") (class "Default")
      (node (ref "U0-C") (pin "112") (pinfunction "PC11_112") (pintype "bidirectional"))
      (node (ref "U1-C") (pin "2") (pinfunction "SO/IO1_2") (pintype "bidirectional"))
    )
    (net (code "35") (name "MOSI-1") (class "Default")
      (node (ref "J2-CS") (pin "3") (pinfunction "3_3") (pintype "passive"))
      (node (ref "U0-C") (pin "43") (pinfunction "PA7_43") (pintype "bidirectional"))
    )
    (net (code "36") (name "MOSI-3") (class "Default")
      (node (ref "U0-C") (pin "113") (pinfunction "PC12_113") (pintype "bidirectional"))
      (node (ref "U1-C") (pin "4") (pinfunction "SI/IO0_4") (pintype "bidirectional"))
    )
    (net (code "37") (name "NRST") (class "Default")
      (node (ref "C15-0C") (pin "1") (pinfunction "1_1") (pintype "passive"))
      (node (ref "R2-J1C") (pin "2") (pinfunction "2_2") (pintype "passive"))
      (node (ref "S1-0C") (pin "1") (pinfunction "S_1") (pintype "passive"))
      (node (ref "S1-0C") (pin "2") (pinfunction "S1_2") (pintype "passive"))
      (node (ref "U0-C") (pin "25") (pinfunction "NRST_25") (pintype "input"))
    )
    (net (code "38") (name "Net-(D0A-C-PadA)") (class "Default")
      (node (ref "D0A-C") (pin "A") (pinfunction "A_A") (pintype "passive"))
      (node (ref "R0A-C") (pin "2") (pinfunction "2_2") (pintype "passive"))
    )
    (net (code "39") (name "Net-(D0B-C-PadA)") (class "Default")
      (node (ref "D0B-C") (pin "A") (pinfunction "A_A") (pintype "passive"))
      (node (ref "R0B-C") (pin "2") (pinfunction "2_2") (pintype "passive"))
    )
    (net (code "40") (name "Net-(D0C-C-PadA)") (class "Default")
      (node (ref "D0C-C") (pin "A") (pinfunction "A_A") (pintype "passive"))
      (node (ref "R0C-C") (pin "2") (pinfunction "2_2") (pintype "passive"))
    )
    (net (code "41") (name "Net-(D1A-C-PadA)") (class "Default")
      (node (ref "D1A-C") (pin "A") (pinfunction "A_A") (pintype "passive"))
      (node (ref "R1A-C") (pin "2") (pinfunction "2_2") (pintype "passive"))
    )
    (net (code "42") (name "Net-(D1B-C-PadA)") (class "Default")
      (node (ref "D1B-C") (pin "A") (pinfunction "A_A") (pintype "passive"))
      (node (ref "R1B-C") (pin "2") (pinfunction "2_2") (pintype "passive"))
    )
    (net (code "43") (name "Net-(D2A-C-PadA)") (class "Default")
      (node (ref "D2A-C") (pin "A") (pinfunction "A_A") (pintype "passive"))
      (node (ref "R2A-C") (pin "2") (pinfunction "2_2") (pintype "passive"))
    )
    (net (code "44") (name "Net-(D2B-C-PadA)") (class "Default")
      (node (ref "D2B-C") (pin "A") (pinfunction "A_A") (pintype "passive"))
      (node (ref "R2B-C") (pin "2") (pinfunction "2_2") (pintype "passive"))
    )
    (net (code "45") (name "Net-(D3-C-PadA)") (class "Default")
      (node (ref "D3-C") (pin "A") (pinfunction "A_A") (pintype "passive"))
      (node (ref "R3-C") (pin "2") (pinfunction "2_2") (pintype "passive"))
    )
    (net (code "46") (name "Net-(D4-C-PadA)") (class "Default")
      (node (ref "D4-C") (pin "A") (pinfunction "A_A") (pintype "passive"))
      (node (ref "R4-C") (pin "2") (pinfunction "2_2") (pintype "passive"))
    )
    (net (code "47") (name "Net-(D5-C-PadA)") (class "Default")
      (node (ref "D5-C") (pin "A") (pinfunction "A_A") (pintype "passive"))
      (node (ref "R5-C") (pin "2") (pinfunction "2_2") (pintype "passive"))
    )
    (net (code "48") (name "Net-(D6-C-PadA)") (class "Default")
      (node (ref "D6-C") (pin "A") (pinfunction "A_A") (pintype "passive"))
      (node (ref "R6-C") (pin "2") (pinfunction "2_2") (pintype "passive"))
    )
    (net (code "49") (name "Net-(J1-C-Pad2)") (class "Default")
      (node (ref "J1-C") (pin "2") (pinfunction "2_2") (pintype "passive"))
      (node (ref "R4-J1C") (pin "1") (pinfunction "1_1") (pintype "passive"))
    )
    (net (code "50") (name "Net-(J1-C-Pad3)") (class "Default")
      (node (ref "J1-C") (pin "3") (pinfunction "3_3") (pintype "passive"))
      (node (ref "R3-J1C") (pin "1") (pinfunction "1_1") (pintype "passive"))
    )
    (net (code "51") (name "Net-(J1-C-Pad5)") (class "Default")
      (node (ref "J1-C") (pin "5") (pinfunction "5_5") (pintype "passive"))
      (node (ref "R1-J1C") (pin "1") (pinfunction "1_1") (pintype "passive"))
    )
    (net (code "52") (name "Net-(J1-C-Pad6)") (class "Default")
      (node (ref "J1-C") (pin "6") (pinfunction "6_6") (pintype "passive"))
      (node (ref "R2-J1C") (pin "1") (pinfunction "1_1") (pintype "passive"))
    )
    (net (code "53") (name "Net-(J2-C-D+)") (class "Default")
      (node (ref "J2-C") (pin "3") (pinfunction "D+_3") (pintype "bidirectional"))
      (node (ref "R2-J2C") (pin "1") (pinfunction "1_1") (pintype "passive"))
    )
    (net (code "54") (name "Net-(J2-C-D-)") (class "Default")
      (node (ref "J2-C") (pin "2") (pinfunction "D-_2") (pintype "bidirectional"))
      (node (ref "R1-J2C") (pin "1") (pinfunction "1_1") (pintype "passive"))
    )
    (net (code "55") (name "Net-(LS1-C-PadV+)") (class "Default")
      (node (ref "LS1-C") (pin "V+") (pinfunction "V+_V+") (pintype "bidirectional"))
      (node (ref "R2-LS1C") (pin "1") (pinfunction "1_1") (pintype "passive"))
    )
    (net (code "56") (name "Net-(Q1-LS1C-B)") (class "Default")
      (node (ref "Q1-LS1C") (pin "1") (pinfunction "B_1") (pintype "passive"))
      (node (ref "R1-LS1C") (pin "2") (pinfunction "2_2") (pintype "passive"))
    )
    (net (code "57") (name "Net-(Q1-LS1C-C)") (class "Default")
      (node (ref "LS1-C") (pin "V-") (pinfunction "V-_V-") (pintype "bidirectional"))
      (node (ref "Q1-LS1C") (pin "2") (pinfunction "C_2") (pintype "passive"))
    )
    (net (code "58") (name "Net-(R2-LS1C-Pad2)") (class "Default")
      (node (ref "R2-LS1C") (pin "2") (pinfunction "2_2") (pintype "passive"))
      (node (ref "VR1-LS1C") (pin "S") (pinfunction "S_S") (pintype "passive"))
    )
    (net (code "59") (name "Net-(R3-LS1C-Pad2)") (class "Default")
      (node (ref "R3-LS1C") (pin "2") (pinfunction "2_2") (pintype "passive"))
      (node (ref "VR1-LS1C") (pin "E") (pinfunction "E_E") (pintype "passive"))
    )
    (net (code "60") (name "Net-(U0-C-BOOT0)") (class "Default")
      (node (ref "R1-0C") (pin "1") (pinfunction "1_1") (pintype "passive"))
      (node (ref "U0-C") (pin "138") (pinfunction "BOOT0_138") (pintype "bidirectional"))
    )
    (net (code "61") (name "Net-(U0-C-VCAP_1)") (class "Default")
      (node (ref "C16-0C") (pin "1") (pinfunction "1_1") (pintype "passive"))
      (node (ref "U0-C") (pin "71") (pinfunction "VCAP_1_71") (pintype "bidirectional"))
    )
    (net (code "62") (name "Net-(U0-C-VCAP_2)") (class "Default")
      (node (ref "C17-0C") (pin "1") (pinfunction "1_1") (pintype "passive"))
      (node (ref "U0-C") (pin "106") (pinfunction "VCAP_2_106") (pintype "bidirectional"))
    )
    (net (code "63") (name "Net-(U2-C-ADDR)") (class "Default")
      (node (ref "R3-2C") (pin "2") (pinfunction "2_2") (pintype "passive"))
      (node (ref "U2-C") (pin "1") (pinfunction "ADDR_1") (pintype "bidirectional"))
    )
    (net (code "64") (name "OSC_IN") (class "Default")
      (node (ref "C1-Y1C") (pin "1") (pinfunction "1_1") (pintype "passive"))
      (node (ref "U0-C") (pin "23") (pinfunction "PH0_23") (pintype "bidirectional"))
      (node (ref "Y1-C") (pin "P$2") (pinfunction "2_P$2") (pintype "passive"))
    )
    (net (code "65") (name "OSC_OUT") (class "Default")
      (node (ref "C2-Y1C") (pin "1") (pinfunction "1_1") (pintype "passive"))
      (node (ref "U0-C") (pin "24") (pinfunction "PH1_24") (pintype "bidirectional"))
      (node (ref "Y1-C") (pin "P$1") (pinfunction "1_P$1") (pintype "passive"))
    )
    (net (code "66") (name "RTS") (class "Default")
      (node (ref "J1-CP") (pin "1") (pinfunction "1_1") (pintype "passive"))
      (node (ref "U0-C") (pin "35") (pinfunction "PA1_35") (pintype "bidirectional"))
    )
    (net (code "67") (name "SCL-1") (class "Default")
      (node (ref "R2-2C") (pin "2") (pinfunction "2_2") (pintype "passive"))
      (node (ref "U0-C") (pin "100") (pinfunction "PA8_100") (pintype "bidirectional"))
      (node (ref "U2-C") (pin "10") (pinfunction "SCL_10") (pintype "bidirectional"))
    )
    (net (code "68") (name "SDA-1") (class "Default")
      (node (ref "R1-2C") (pin "2") (pinfunction "2_2") (pintype "passive"))
      (node (ref "U0-C") (pin "99") (pinfunction "PC9_99") (pintype "bidirectional"))
      (node (ref "U2-C") (pin "9") (pinfunction "SDA_9") (pintype "bidirectional"))
    )
    (net (code "69") (name "SENSE_A") (class "Default")
      (node (ref "J3-CP") (pin "1") (pinfunction "1_1") (pintype "passive"))
      (node (ref "U0-C") (pin "18") (pinfunction "PF6_18") (pintype "bidirectional"))
      (node (ref "U2-C") (pin "4") (pinfunction "AIN0_4") (pintype "bidirectional"))
    )
    (net (code "70") (name "SENSE_B") (class "Default")
      (node (ref "J3-CP") (pin "2") (pinfunction "2_2") (pintype "passive"))
      (node (ref "U0-C") (pin "19") (pinfunction "PF7_19") (pintype "bidirectional"))
      (node (ref "U2-C") (pin "5") (pinfunction "AIN1_5") (pintype "bidirectional"))
    )
    (net (code "71") (name "SENSE_C") (class "Default")
      (node (ref "J3-CP") (pin "3") (pinfunction "3_3") (pintype "passive"))
      (node (ref "U0-C") (pin "20") (pinfunction "PF8_20") (pintype "bidirectional"))
      (node (ref "U2-C") (pin "6") (pinfunction "AIN2_6") (pintype "bidirectional"))
    )
    (net (code "72") (name "SENSE_D") (class "Default")
      (node (ref "J3-CP") (pin "4") (pinfunction "4_4") (pintype "passive"))
      (node (ref "U0-C") (pin "21") (pinfunction "PF9_21") (pintype "bidirectional"))
      (node (ref "U2-C") (pin "7") (pinfunction "AIN3_7") (pintype "bidirectional"))
    )
    (net (code "73") (name "SENSOR-ERROR") (class "Default")
      (node (ref "J3-CS") (pin "2") (pinfunction "2_2") (pintype "passive"))
      (node (ref "U0-C") (pin "64") (pinfunction "PE11_64") (pintype "bidirectional"))
    )
    (net (code "74") (name "SENSOR-NOMINAL") (class "Default")
      (node (ref "J3-CS") (pin "1") (pinfunction "1_1") (pintype "passive"))
      (node (ref "U0-C") (pin "63") (pinfunction "PE10_63") (pintype "bidirectional"))
    )
    (net (code "75") (name "STORAGE-ERROR") (class "Default")
      (node (ref "R5-C") (pin "1") (pinfunction "1_1") (pintype "passive"))
      (node (ref "U0-C") (pin "58") (pinfunction "PE7_58") (pintype "bidirectional"))
    )
    (net (code "76") (name "SWCLK") (class "Default")
      (node (ref "R4-J1C") (pin "2") (pinfunction "2_2") (pintype "passive"))
      (node (ref "U0-C") (pin "109") (pinfunction "PA14_109") (pintype "bidirectional"))
    )
    (net (code "77") (name "SWDIO") (class "Default")
      (node (ref "R3-J1C") (pin "2") (pinfunction "2_2") (pintype "passive"))
      (node (ref "U0-C") (pin "105") (pinfunction "PA13_105") (pintype "bidirectional"))
    )
    (net (code "78") (name "SWO") (class "Default")
      (node (ref "R1-J1C") (pin "2") (pinfunction "2_2") (pintype "passive"))
      (node (ref "U0-C") (pin "133") (pinfunction "PB3_133") (pintype "bidirectional"))
    )
    (net (code "79") (name "U1S-CHECK") (class "Default")
      (node (ref "J3-CS") (pin "3") (pinfunction "3_3") (pintype "passive"))
      (node (ref "U0-C") (pin "65") (pinfunction "PE12_65") (pintype "bidirectional"))
    )
    (net (code "80") (name "U2S-CHECK") (class "Default")
      (node (ref "J3-CS") (pin "4") (pinfunction "4_4") (pintype "passive"))
      (node (ref "U0-C") (pin "66") (pinfunction "PE13_66") (pintype "bidirectional"))
    )
    (net (code "81") (name "U2S-ST") (class "Default")
      (node (ref "J3-CS") (pin "7") (pinfunction "7_7") (pintype "passive"))
      (node (ref "U0-C") (pin "69") (pinfunction "PB10_69") (pintype "bidirectional"))
    )
    (net (code "82") (name "U3S-CHECK") (class "Default")
      (node (ref "J3-CS") (pin "5") (pinfunction "5_5") (pintype "passive"))
      (node (ref "U0-C") (pin "67") (pinfunction "PE14_67") (pintype "bidirectional"))
    )
    (net (code "83") (name "U4S-CHECK") (class "Default")
      (node (ref "J3-CS") (pin "6") (pinfunction "6_6") (pintype "passive"))
      (node (ref "U0-C") (pin "68") (pinfunction "PE15_68") (pintype "bidirectional"))
    )
    (net (code "84") (name "US2-STATUS") (class "Default")
      (node (ref "J3-CS") (pin "8") (pinfunction "8_8") (pintype "passive"))
      (node (ref "U0-C") (pin "70") (pinfunction "PB11_70") (pintype "bidirectional"))
    )
    (net (code "85") (name "VDDA") (class "Default")
      (node (ref "FB1-0C") (pin "2") (pinfunction "2_2") (pintype "bidirectional"))
      (node (ref "U0-C") (pin "32") (pinfunction "VREF+_32") (pintype "input"))
      (node (ref "U0-C") (pin "33") (pinfunction "VDDA_33") (pintype "power_in"))
    )
    (net (code "86") (name "VUSB") (class "Default")
      (node (ref "J2-C") (pin "1") (pinfunction "VBUS_1") (pintype "power_in"))
      (node (ref "JP-CP") (pin "4") (pinfunction "4_4") (pintype "passive"))
    )
    (net (code "87") (name "WP") (class "Default")
      (node (ref "U0-C") (pin "115") (pinfunction "PD1_115") (pintype "bidirectional"))
      (node (ref "U1-C") (pin "3") (pinfunction "~{WP}/IO2_3") (pintype "bidirectional"))
    )
    (net (code "88") (name "unconnected-(JP-CS-Pad4)") (class "Default")
      (node (ref "JP-CS") (pin "4") (pinfunction "4_4") (pintype "passive"))
    )
    (net (code "89") (name "unconnected-(S0-0C-P1-Pad4)") (class "Default")
      (node (ref "S0-0C") (pin "4") (pinfunction "P1_4") (pintype "passive"))
    )
    (net (code "90") (name "unconnected-(S0-0C-S1-Pad2)") (class "Default")
      (node (ref "S0-0C") (pin "2") (pinfunction "S1_2") (pintype "passive"))
    )
    (net (code "91") (name "unconnected-(U0-C-PA4-Pad40)") (class "Default")
      (node (ref "U0-C") (pin "40") (pinfunction "PA4_40") (pintype "bidirectional"))
    )
    (net (code "92") (name "unconnected-(U0-C-PA9-Pad101)") (class "Default")
      (node (ref "U0-C") (pin "101") (pinfunction "PA9_101") (pintype "bidirectional"))
    )
    (net (code "93") (name "unconnected-(U0-C-PA15-Pad110)") (class "Default")
      (node (ref "U0-C") (pin "110") (pinfunction "PA15_110") (pintype "bidirectional"))
    )
    (net (code "94") (name "unconnected-(U0-C-PB2-Pad48)") (class "Default")
      (node (ref "U0-C") (pin "48") (pinfunction "PB2_48") (pintype "bidirectional"))
    )
    (net (code "95") (name "unconnected-(U0-C-PB4-Pad134)") (class "Default")
      (node (ref "U0-C") (pin "134") (pinfunction "PB4_134") (pintype "bidirectional"))
    )
    (net (code "96") (name "unconnected-(U0-C-PB5-Pad135)") (class "Default")
      (node (ref "U0-C") (pin "135") (pinfunction "PB5_135") (pintype "bidirectional"))
    )
    (net (code "97") (name "unconnected-(U0-C-PB6-Pad136)") (class "Default")
      (node (ref "U0-C") (pin "136") (pinfunction "PB6_136") (pintype "bidirectional"))
    )
    (net (code "98") (name "unconnected-(U0-C-PB7-Pad137)") (class "Default")
      (node (ref "U0-C") (pin "137") (pinfunction "PB7_137") (pintype "bidirectional"))
    )
    (net (code "99") (name "unconnected-(U0-C-PB8-Pad139)") (class "Default")
      (node (ref "U0-C") (pin "139") (pinfunction "PB8_139") (pintype "bidirectional"))
    )
    (net (code "100") (name "unconnected-(U0-C-PB9-Pad140)") (class "Default")
      (node (ref "U0-C") (pin "140") (pinfunction "PB9_140") (pintype "bidirectional"))
    )
    (net (code "101") (name "unconnected-(U0-C-PB12-Pad73)") (class "Default")
      (node (ref "U0-C") (pin "73") (pinfunction "PB12_73") (pintype "bidirectional"))
    )
    (net (code "102") (name "unconnected-(U0-C-PB13-Pad74)") (class "Default")
      (node (ref "U0-C") (pin "74") (pinfunction "PB13_74") (pintype "bidirectional"))
    )
    (net (code "103") (name "unconnected-(U0-C-PB14-Pad75)") (class "Default")
      (node (ref "U0-C") (pin "75") (pinfunction "PB14_75") (pintype "bidirectional"))
    )
    (net (code "104") (name "unconnected-(U0-C-PB15-Pad76)") (class "Default")
      (node (ref "U0-C") (pin "76") (pinfunction "PB15_76") (pintype "bidirectional"))
    )
    (net (code "105") (name "unconnected-(U0-C-PC0-Pad26)") (class "Default")
      (node (ref "U0-C") (pin "26") (pinfunction "PC0_26") (pintype "bidirectional"))
    )
    (net (code "106") (name "unconnected-(U0-C-PC1-Pad27)") (class "Default")
      (node (ref "U0-C") (pin "27") (pinfunction "PC1_27") (pintype "bidirectional"))
    )
    (net (code "107") (name "unconnected-(U0-C-PC2-Pad28)") (class "Default")
      (node (ref "U0-C") (pin "28") (pinfunction "PC2_28") (pintype "bidirectional"))
    )
    (net (code "108") (name "unconnected-(U0-C-PC3-Pad29)") (class "Default")
      (node (ref "U0-C") (pin "29") (pinfunction "PC3_29") (pintype "bidirectional"))
    )
    (net (code "109") (name "unconnected-(U0-C-PC13-Pad7)") (class "Default")
      (node (ref "U0-C") (pin "7") (pinfunction "PC13_7") (pintype "bidirectional"))
    )
    (net (code "110") (name "unconnected-(U0-C-PC14-Pad8)") (class "Default")
      (node (ref "U0-C") (pin "8") (pinfunction "PC14_8") (pintype "bidirectional"))
    )
    (net (code "111") (name "unconnected-(U0-C-PC15-Pad9)") (class "Default")
      (node (ref "U0-C") (pin "9") (pinfunction "PC15_9") (pintype "bidirectional"))
    )
    (net (code "112") (name "unconnected-(U0-C-PD3-Pad117)") (class "Default")
      (node (ref "U0-C") (pin "117") (pinfunction "PD3_117") (pintype "bidirectional"))
    )
    (net (code "113") (name "unconnected-(U0-C-PD4-Pad118)") (class "Default")
      (node (ref "U0-C") (pin "118") (pinfunction "PD4_118") (pintype "bidirectional"))
    )
    (net (code "114") (name "unconnected-(U0-C-PD5-Pad119)") (class "Default")
      (node (ref "U0-C") (pin "119") (pinfunction "PD5_119") (pintype "bidirectional"))
    )
    (net (code "115") (name "unconnected-(U0-C-PD6-Pad122)") (class "Default")
      (node (ref "U0-C") (pin "122") (pinfunction "PD6_122") (pintype "bidirectional"))
    )
    (net (code "116") (name "unconnected-(U0-C-PD7-Pad123)") (class "Default")
      (node (ref "U0-C") (pin "123") (pinfunction "PD7_123") (pintype "bidirectional"))
    )
    (net (code "117") (name "unconnected-(U0-C-PD8-Pad77)") (class "Default")
      (node (ref "U0-C") (pin "77") (pinfunction "PD8_77") (pintype "bidirectional"))
    )
    (net (code "118") (name "unconnected-(U0-C-PD9-Pad78)") (class "Default")
      (node (ref "U0-C") (pin "78") (pinfunction "PD9_78") (pintype "bidirectional"))
    )
    (net (code "119") (name "unconnected-(U0-C-PD10-Pad79)") (class "Default")
      (node (ref "U0-C") (pin "79") (pinfunction "PD10_79") (pintype "bidirectional"))
    )
    (net (code "120") (name "unconnected-(U0-C-PD11-Pad80)") (class "Default")
      (node (ref "U0-C") (pin "80") (pinfunction "PD11_80") (pintype "bidirectional"))
    )
    (net (code "121") (name "unconnected-(U0-C-PD12-Pad81)") (class "Default")
      (node (ref "U0-C") (pin "81") (pinfunction "PD12_81") (pintype "bidirectional"))
    )
    (net (code "122") (name "unconnected-(U0-C-PD13-Pad82)") (class "Default")
      (node (ref "U0-C") (pin "82") (pinfunction "PD13_82") (pintype "bidirectional"))
    )
    (net (code "123") (name "unconnected-(U0-C-PD14-Pad85)") (class "Default")
      (node (ref "U0-C") (pin "85") (pinfunction "PD14_85") (pintype "bidirectional"))
    )
    (net (code "124") (name "unconnected-(U0-C-PD15-Pad86)") (class "Default")
      (node (ref "U0-C") (pin "86") (pinfunction "PD15_86") (pintype "bidirectional"))
    )
    (net (code "125") (name "unconnected-(U0-C-PE0-Pad141)") (class "Default")
      (node (ref "U0-C") (pin "141") (pinfunction "PE0_141") (pintype "bidirectional"))
    )
    (net (code "126") (name "unconnected-(U0-C-PE1-Pad142)") (class "Default")
      (node (ref "U0-C") (pin "142") (pinfunction "PE1_142") (pintype "bidirectional"))
    )
    (net (code "127") (name "unconnected-(U0-C-PE3-Pad2)") (class "Default")
      (node (ref "U0-C") (pin "2") (pinfunction "PE3_2") (pintype "bidirectional"))
    )
    (net (code "128") (name "unconnected-(U0-C-PE4-Pad3)") (class "Default")
      (node (ref "U0-C") (pin "3") (pinfunction "PE4_3") (pintype "bidirectional"))
    )
    (net (code "129") (name "unconnected-(U0-C-PE5-Pad4)") (class "Default")
      (node (ref "U0-C") (pin "4") (pinfunction "PE5_4") (pintype "bidirectional"))
    )
    (net (code "130") (name "unconnected-(U0-C-PE6-Pad5)") (class "Default")
      (node (ref "U0-C") (pin "5") (pinfunction "PE6_5") (pintype "bidirectional"))
    )
    (net (code "131") (name "unconnected-(U0-C-PE9-Pad60)") (class "Default")
      (node (ref "U0-C") (pin "60") (pinfunction "PE9_60") (pintype "bidirectional"))
    )
    (net (code "132") (name "unconnected-(U0-C-PF0-Pad10)") (class "Default")
      (node (ref "U0-C") (pin "10") (pinfunction "PF0_10") (pintype "bidirectional"))
    )
    (net (code "133") (name "unconnected-(U0-C-PF5-Pad15)") (class "Default")
      (node (ref "U0-C") (pin "15") (pinfunction "PF5_15") (pintype "bidirectional"))
    )
    (net (code "134") (name "unconnected-(U0-C-PF10-Pad22)") (class "Default")
      (node (ref "U0-C") (pin "22") (pinfunction "PF10_22") (pintype "bidirectional"))
    )
    (net (code "135") (name "unconnected-(U0-C-PF11-Pad49)") (class "Default")
      (node (ref "U0-C") (pin "49") (pinfunction "PF11_49") (pintype "bidirectional"))
    )
    (net (code "136") (name "unconnected-(U0-C-PF12-Pad50)") (class "Default")
      (node (ref "U0-C") (pin "50") (pinfunction "PF12_50") (pintype "bidirectional"))
    )
    (net (code "137") (name "unconnected-(U0-C-PG2-Pad87)") (class "Default")
      (node (ref "U0-C") (pin "87") (pinfunction "PG2_87") (pintype "bidirectional"))
    )
    (net (code "138") (name "unconnected-(U0-C-PG3-Pad88)") (class "Default")
      (node (ref "U0-C") (pin "88") (pinfunction "PG3_88") (pintype "bidirectional"))
    )
    (net (code "139") (name "unconnected-(U0-C-PG5-Pad90)") (class "Default")
      (node (ref "U0-C") (pin "90") (pinfunction "PG5_90") (pintype "bidirectional"))
    )
    (net (code "140") (name "unconnected-(U0-C-PG6-Pad91)") (class "Default")
      (node (ref "U0-C") (pin "91") (pinfunction "PG6_91") (pintype "bidirectional"))
    )
    (net (code "141") (name "unconnected-(U0-C-PG7-Pad92)") (class "Default")
      (node (ref "U0-C") (pin "92") (pinfunction "PG7_92") (pintype "bidirectional"))
    )
    (net (code "142") (name "unconnected-(U0-C-PG8-Pad93)") (class "Default")
      (node (ref "U0-C") (pin "93") (pinfunction "PG8_93") (pintype "bidirectional"))
    )
    (net (code "143") (name "unconnected-(U0-C-PG9-Pad124)") (class "Default")
      (node (ref "U0-C") (pin "124") (pinfunction "PG9_124") (pintype "bidirectional"))
    )
    (net (code "144") (name "unconnected-(U0-C-PG10-Pad125)") (class "Default")
      (node (ref "U0-C") (pin "125") (pinfunction "PG10_125") (pintype "bidirectional"))
    )
    (net (code "145") (name "unconnected-(U0-C-PG11-Pad126)") (class "Default")
      (node (ref "U0-C") (pin "126") (pinfunction "PG11_126") (pintype "bidirectional"))
    )
    (net (code "146") (name "unconnected-(U0-C-PG12-Pad127)") (class "Default")
      (node (ref "U0-C") (pin "127") (pinfunction "PG12_127") (pintype "bidirectional"))
    )
    (net (code "147") (name "unconnected-(U0-C-PG13-Pad128)") (class "Default")
      (node (ref "U0-C") (pin "128") (pinfunction "PG13_128") (pintype "bidirectional"))
    )
    (net (code "148") (name "unconnected-(U0-C-PG14-Pad129)") (class "Default")
      (node (ref "U0-C") (pin "129") (pinfunction "PG14_129") (pintype "bidirectional"))
    )
    (net (code "149") (name "unconnected-(U0-C-PG15-Pad132)") (class "Default")
      (node (ref "U0-C") (pin "132") (pinfunction "PG15_132") (pintype "bidirectional"))
    )
    (net (code "150") (name "unconnected-(U1-C-EP-Pad9)") (class "Default")
      (node (ref "U1-C") (pin "9") (pinfunction "EP_9") (pintype "bidirectional"))
    )
  )
)
